# WR_Cute_Carrier_TOP.net
KiCad netlist of a schematic drawn in Altium Designer
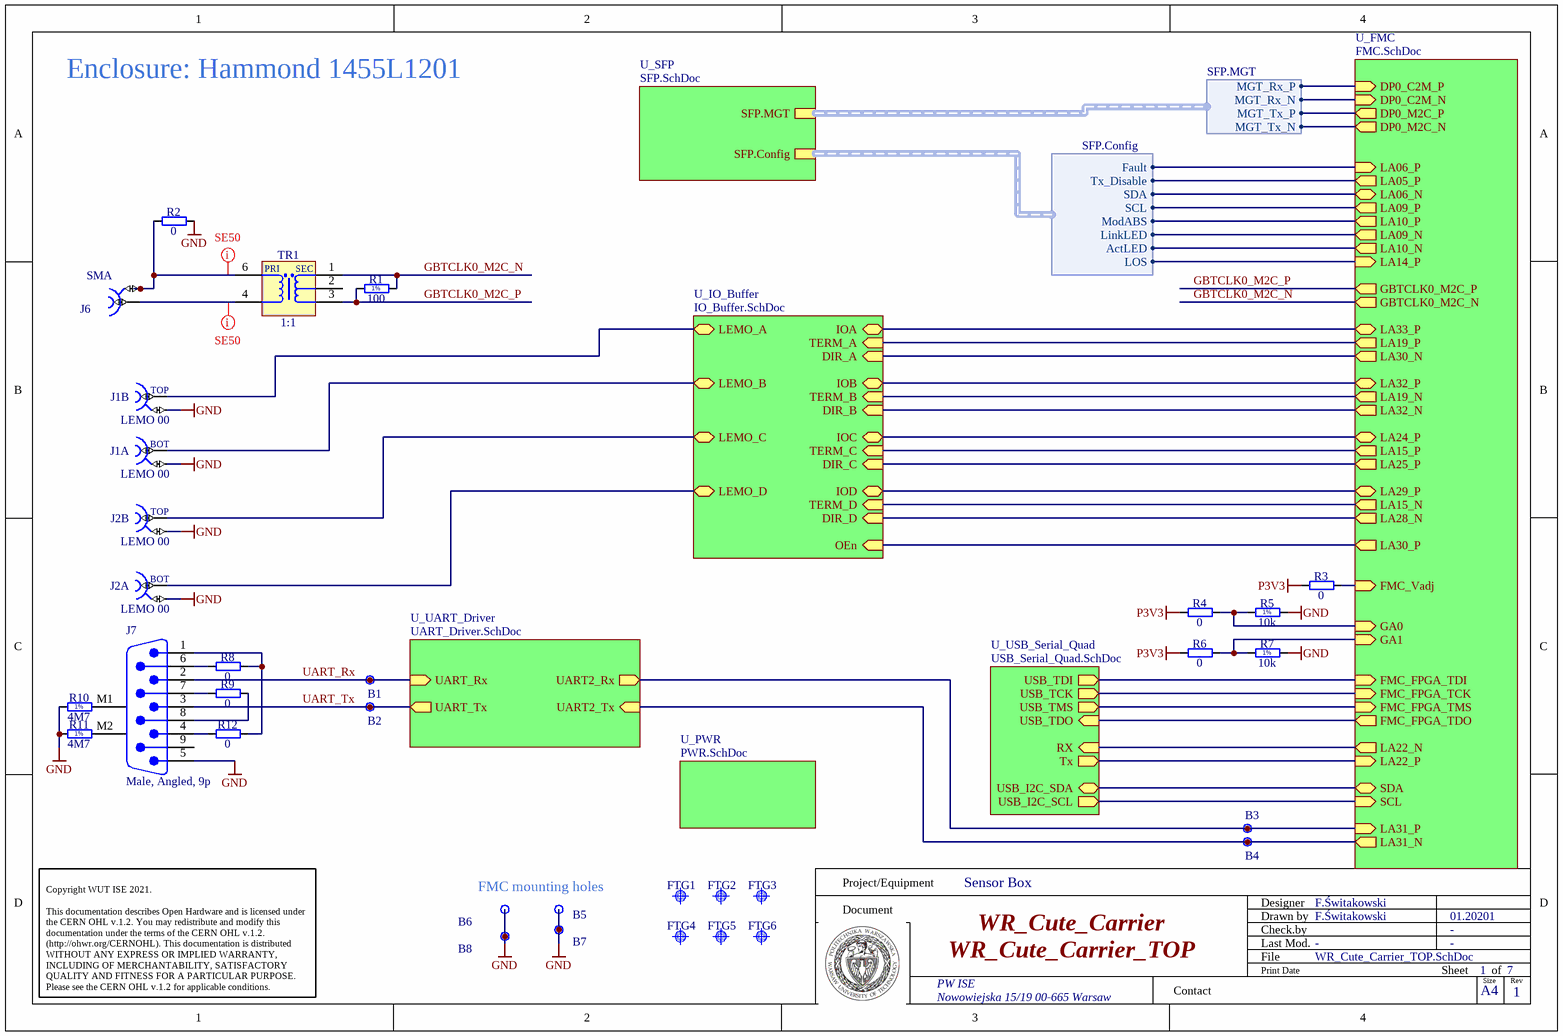
[diagram p0: WR_Cute_Carrier_TOP.SchDoc]

(export (version "E")
  (design (tool "Eeschema 10.0.6"))
  (components
    (comp (ref "B1")
      (value "Plated Hole")
      (footprint "c130h60")
      (description "Single Terminal Socket")
      (fields (field (name "PART NUMBER") "PLATED_HOLE0.6_PAD1.3") (field (name "AUTHOR") "CERN DEM MR"))
      (libsource (lib "Eletro-mechanical") (part "Single Terminal Socket"))
    )
    (comp (ref "B2")
      (value "Plated Hole")
      (footprint "c130h60")
      (description "Single Terminal Socket")
      (fields (field (name "PART NUMBER") "PLATED_HOLE0.6_PAD1.3") (field (name "AUTHOR") "CERN DEM MR"))
      (libsource (lib "Eletro-mechanical") (part "Single Terminal Socket"))
    )
    (comp (ref "B3")
      (value "Plated Hole")
      (footprint "c130h60")
      (description "Single Terminal Socket")
      (fields (field (name "PART NUMBER") "PLATED_HOLE0.6_PAD1.3") (field (name "AUTHOR") "CERN DEM MR"))
      (libsource (lib "Eletro-mechanical") (part "Single Terminal Socket"))
    )
    (comp (ref "B4")
      (value "Plated Hole")
      (footprint "c130h60")
      (description "Single Terminal Socket")
      (fields (field (name "PART NUMBER") "PLATED_HOLE0.6_PAD1.3") (field (name "AUTHOR") "CERN DEM MR"))
      (libsource (lib "Eletro-mechanical") (part "Single Terminal Socket"))
    )
    (comp (ref "B5")
      (value "Plated Hole")
      (footprint "MTG270_500")
      (description "Single Terminal Socket")
      (fields (field (name "PART NUMBER") "PLATED_HOLE2.7_PAD5.0") (field (name "AUTHOR") "CERN DEM JMW"))
      (libsource (lib "Eletro-mechanical") (part "Single Terminal Socket"))
    )
    (comp (ref "B6")
      (value "Plated Hole")
      (footprint "MTG270_500")
      (description "Single Terminal Socket")
      (fields (field (name "PART NUMBER") "PLATED_HOLE2.7_PAD5.0") (field (name "AUTHOR") "CERN DEM JMW"))
      (libsource (lib "Eletro-mechanical") (part "Single Terminal Socket"))
    )
    (comp (ref "B7")
      (value "Plated Hole")
      (footprint "MTG270_500")
      (description "Single Terminal Socket")
      (fields (field (name "PART NUMBER") "PLATED_HOLE2.7_PAD5.0") (field (name "AUTHOR") "CERN DEM JMW"))
      (libsource (lib "Eletro-mechanical") (part "Single Terminal Socket"))
    )
    (comp (ref "B8")
      (value "Plated Hole")
      (footprint "MTG270_500")
      (description "Single Terminal Socket")
      (fields (field (name "PART NUMBER") "PLATED_HOLE2.7_PAD5.0") (field (name "AUTHOR") "CERN DEM JMW"))
      (libsource (lib "Eletro-mechanical") (part "Single Terminal Socket"))
    )
    (comp (ref "FTG1")
      (value "Use only in PCB")
      (footprint "FIDUCIAL_TOP_S100-200")
      (description "Fiducial Target")
      (fields (field (name "PART NUMBER") "FIDUCIAL_TARGET_S100-200") (field (name "AUTHOR") "CERN DEM JLC"))
      (libsource (lib "Eletro-mechanical") (part "Fiducial Target"))
    )
    (comp (ref "FTG2")
      (value "Use only in PCB")
      (footprint "FIDUCIAL_TOP_S100-200")
      (description "Fiducial Target")
      (fields (field (name "PART NUMBER") "FIDUCIAL_TARGET_S100-200") (field (name "AUTHOR") "CERN DEM JLC"))
      (libsource (lib "Eletro-mechanical") (part "Fiducial Target"))
    )
    (comp (ref "FTG3")
      (value "Use only in PCB")
      (footprint "FIDUCIAL_TOP_S100-200")
      (description "Fiducial Target")
      (fields (field (name "PART NUMBER") "FIDUCIAL_TARGET_S100-200") (field (name "AUTHOR") "CERN DEM JLC"))
      (libsource (lib "Eletro-mechanical") (part "Fiducial Target"))
    )
    (comp (ref "FTG4")
      (value "Use only in PCB")
      (footprint "FIDUCIAL_TOP_S100-200")
      (description "Fiducial Target")
      (fields (field (name "PART NUMBER") "FIDUCIAL_TARGET_S100-200") (field (name "AUTHOR") "CERN DEM JLC"))
      (libsource (lib "Eletro-mechanical") (part "Fiducial Target"))
    )
    (comp (ref "FTG5")
      (value "Use only in PCB")
      (footprint "FIDUCIAL_TOP_S100-200")
      (description "Fiducial Target")
      (fields (field (name "PART NUMBER") "FIDUCIAL_TARGET_S100-200") (field (name "AUTHOR") "CERN DEM JLC"))
      (libsource (lib "Eletro-mechanical") (part "Fiducial Target"))
    )
    (comp (ref "FTG6")
      (value "Use only in PCB")
      (footprint "FIDUCIAL_TOP_S100-200")
      (description "Fiducial Target")
      (fields (field (name "PART NUMBER") "FIDUCIAL_TARGET_S100-200") (field (name "AUTHOR") "CERN DEM JLC"))
      (libsource (lib "Eletro-mechanical") (part "Fiducial Target"))
    )
    (comp (ref "J1")
      (value "LEMO 00")
      (footprint "LEMO_EPY.00.250.NTN")
      (description "Dual Female Coax 1-2 Common Shield 3")
      (fields
        (field (name "PART NUMBER") "LEMO_EPY.00.250.NTN")
        (field (name "MANUFACTURER") "LEMO")
        (field (name "AUTHOR") "CERN DEM JMW")
      )
      (libsource (lib "Connectors") (part "LEMO_EPY.00.250.NTN"))
    )
    (comp (ref "J2")
      (value "LEMO 00")
      (footprint "LEMO_EPY.00.250.NTN")
      (description "Dual Female Coax 1-2 Common Shield 3")
      (fields
        (field (name "PART NUMBER") "LEMO_EPY.00.250.NTN")
        (field (name "MANUFACTURER") "LEMO")
        (field (name "AUTHOR") "CERN DEM JMW")
      )
      (libsource (lib "Connectors") (part "LEMO_EPY.00.250.NTN"))
    )
    (comp (ref "J6")
      (value "SMA")
      (footprint "AMPHENOL_132203")
      (fields
        (field (name "PART NUMBER") "AMPHENOL_132203")
        (field (name "MANUFACTURER") "AMPHENOL")
        (field (name "MANUFACTURER PART NUMBER") "132203")
        (field (name "AUTHOR") "CERN DEM MR")
      )
      (libsource (lib "Connectors") (part "Coax_1Female_1Shield"))
    )
    (comp (ref "J7")
      (value "Male, Angled, 9p")
      (footprint "210112013")
      (description "WE-D-SUB Filter Connector, THT, Angled, Male, 9p")
      (fields
        (field (name "MANUFACTURER PART NUMBER") "210112013")
        (field (name "MANUFACTURER") "Wurth Elektronik")
      )
      (libsource (lib "Altium_WE-D-SUB (rev20a)") (part "210112013"))
    )
    (comp (ref "R1")
      (value "100")
      (footprint "RESC2012X60N")
      (description "Resistor - 1%")
      (fields
        (field (name "PART NUMBER") "R0805_100R_1%_0.125W_100PPM")
        (field (name "POWER") "0.125W")
        (field (name "AUTHOR") "CERN DEM JLC")
      )
      (libsource (lib "Resistors") (part "Resistor - 1%"))
    )
    (comp (ref "R2")
      (value "0")
      (footprint "RESC1608X55N")
      (description "Resistor")
      (fields
        (field (name "PART NUMBER") "R0603_0R_JUMPER")
        (field (name "MANUFACTURER") "GENERIC")
        (field (name "AUTHOR") "CERN DEM JLC")
      )
      (libsource (lib "Resistors") (part "Resistor"))
    )
    (comp (ref "R3")
      (value "0")
      (footprint "RESC1608X55N")
      (description "Resistor")
      (fields
        (field (name "PART NUMBER") "R0603_0R_JUMPER")
        (field (name "MANUFACTURER") "GENERIC")
        (field (name "AUTHOR") "CERN DEM JLC")
      )
      (libsource (lib "Resistors") (part "Resistor"))
    )
    (comp (ref "R4")
      (value "0")
      (footprint "RESC1608X55N")
      (description "Resistor")
      (fields
        (field (name "PART NUMBER") "R0603_0R_JUMPER")
        (field (name "MANUFACTURER") "GENERIC")
        (field (name "AUTHOR") "CERN DEM JLC")
      )
      (libsource (lib "Resistors") (part "Resistor"))
    )
    (comp (ref "R5")
      (value "10k")
      (footprint "RESC1608X55N")
      (description "Resistor - 1%")
      (fields
        (field (name "PART NUMBER") "R0603_10K_1%_0.1W_100PPM")
        (field (name "POWER") "0.1W")
        (field (name "AUTHOR") "CERN DEM JLC")
      )
      (libsource (lib "Resistors") (part "Resistor - 1%"))
    )
    (comp (ref "R6")
      (value "0")
      (footprint "RESC1608X55N")
      (description "Resistor")
      (fields
        (field (name "PART NUMBER") "R0603_0R_JUMPER")
        (field (name "MANUFACTURER") "GENERIC")
        (field (name "AUTHOR") "CERN DEM JLC")
      )
      (libsource (lib "Resistors") (part "Resistor"))
    )
    (comp (ref "R7")
      (value "10k")
      (footprint "RESC1608X55N")
      (description "Resistor - 1%")
      (fields
        (field (name "PART NUMBER") "R0603_10K_1%_0.1W_100PPM")
        (field (name "POWER") "0.1W")
        (field (name "AUTHOR") "CERN DEM JLC")
      )
      (libsource (lib "Resistors") (part "Resistor - 1%"))
    )
    (comp (ref "R8")
      (value "0")
      (footprint "RESC1608X55N")
      (description "Resistor")
      (fields
        (field (name "PART NUMBER") "R0603_0R_JUMPER")
        (field (name "MANUFACTURER") "GENERIC")
        (field (name "AUTHOR") "CERN DEM JLC")
      )
      (libsource (lib "Resistors") (part "Resistor"))
    )
    (comp (ref "R9")
      (value "0")
      (footprint "RESC1608X55N")
      (description "Resistor")
      (fields
        (field (name "PART NUMBER") "R0603_0R_JUMPER")
        (field (name "MANUFACTURER") "GENERIC")
        (field (name "AUTHOR") "CERN DEM JLC")
      )
      (libsource (lib "Resistors") (part "Resistor"))
    )
    (comp (ref "R10")
      (value "4M7")
      (footprint "RESC2113X55N")
      (description "Resistor - 1%")
      (fields
        (field (name "PART NUMBER") "R0805_4M7_1%_0.125W_100PPM_VISHAY_CRCW e3")
        (field (name "POWER") "0.125W")
        (field (name "AUTHOR") "CERN DEM BR")
      )
      (libsource (lib "Resistors") (part "Resistor - 1%"))
    )
    (comp (ref "R11")
      (value "4M7")
      (footprint "RESC2113X55N")
      (description "Resistor - 1%")
      (fields
        (field (name "PART NUMBER") "R0805_4M7_1%_0.125W_100PPM_VISHAY_CRCW e3")
        (field (name "POWER") "0.125W")
        (field (name "AUTHOR") "CERN DEM BR")
      )
      (libsource (lib "Resistors") (part "Resistor - 1%"))
    )
    (comp (ref "R12")
      (value "0")
      (footprint "RESC1608X55N")
      (description "Resistor")
      (fields
        (field (name "PART NUMBER") "R0603_0R_JUMPER")
        (field (name "MANUFACTURER") "GENERIC")
        (field (name "AUTHOR") "CERN DEM JLC")
      )
      (libsource (lib "Resistors") (part "Resistor"))
    )
    (comp (ref "TR1")
      (value "1:1")
      (footprint "XFMR_MINI-CIRCUITS_AT1521")
      (description "50 Ohms 3 to 300MHz RF Transformer")
      (fields
        (field (name "PART NUMBER") "XFMR_MINI-CIRCUITS_TC2-1TX+")
        (field (name "MANUFACTURER") "MINI-CIRCUITS")
        (field (name "AUTHOR") "CERN DEM MR")
      )
      (libsource (lib "Inductors & Transformers") (part "XFMR_MINI-CIRCUITS_TC2-1TX+"))
    )
  )
  (nets
    (net (code "8") (name "/FMC_Vadj") (class "Default")
      (node (ref "R3") (pin "2") (pinfunction "2_2") (pintype "passive"))
    )
    (net (code "9") (name "/GA0") (class "Default")
      (node (ref "R4") (pin "2") (pinfunction "2_2") (pintype "passive"))
      (node (ref "R5") (pin "1") (pinfunction "1_1") (pintype "passive"))
    )
    (net (code "10") (name "/GA1") (class "Default")
      (node (ref "R6") (pin "2") (pinfunction "2_2") (pintype "passive"))
      (node (ref "R7") (pin "1") (pinfunction "1_1") (pintype "passive"))
    )
    (net (code "11") (name "/GBTCLK0_M2C_N") (class "Default")
      (node (ref "R1") (pin "2") (pinfunction "2_2") (pintype "passive"))
      (node (ref "TR1") (pin "1") (pinfunction "SDOT_1") (pintype "passive"))
    )
    (net (code "12") (name "/GBTCLK0_M2C_P") (class "Default")
      (node (ref "R1") (pin "1") (pinfunction "1_1") (pintype "passive"))
      (node (ref "TR1") (pin "3") (pinfunction "S_3") (pintype "passive"))
    )
    (net (code "34") (name "/LA31_N") (class "Default")
      (node (ref "B4") (pin "1") (pinfunction "1_1") (pintype "bidirectional"))
    )
    (net (code "36") (name "/LEMO_A") (class "Default")
      (node (ref "J1") (pin "2") (pinfunction "2_2") (pintype "bidirectional"))
    )
    (net (code "37") (name "/LEMO_B") (class "Default")
      (node (ref "J1") (pin "1") (pinfunction "1_1") (pintype "bidirectional"))
    )
    (net (code "38") (name "/LEMO_C") (class "Default")
      (node (ref "J2") (pin "2") (pinfunction "2_2") (pintype "bidirectional"))
    )
    (net (code "39") (name "/LEMO_D") (class "Default")
      (node (ref "J2") (pin "1") (pinfunction "1_1") (pintype "bidirectional"))
    )
    (net (code "42") (name "/UART2_Rx") (class "Default")
      (node (ref "B3") (pin "1") (pinfunction "1_1") (pintype "bidirectional"))
    )
    (net (code "43") (name "/UART_Rx") (class "Default")
      (node (ref "B1") (pin "1") (pinfunction "1_1") (pintype "bidirectional"))
      (node (ref "J7") (pin "2") (pinfunction "2_2") (pintype "passive"))
    )
    (net (code "44") (name "/UART_Tx") (class "Default")
      (node (ref "B2") (pin "1") (pinfunction "1_1") (pintype "bidirectional"))
      (node (ref "J7") (pin "3") (pinfunction "3_3") (pintype "passive"))
    )
    (net (code "51") (name "GND") (class "Default")
      (node (ref "B5") (pin "1") (pinfunction "1_1") (pintype "bidirectional"))
      (node (ref "B6") (pin "1") (pinfunction "1_1") (pintype "bidirectional"))
      (node (ref "B7") (pin "1") (pinfunction "1_1") (pintype "bidirectional"))
      (node (ref "B8") (pin "1") (pinfunction "1_1") (pintype "bidirectional"))
      (node (ref "J1") (pin "3") (pinfunction "3_3") (pintype "bidirectional"))
      (node (ref "J2") (pin "3") (pinfunction "3_3") (pintype "bidirectional"))
      (node (ref "J7") (pin "5") (pinfunction "5_5") (pintype "passive"))
      (node (ref "R10") (pin "1") (pinfunction "1_1") (pintype "passive"))
      (node (ref "R11") (pin "1") (pinfunction "1_1") (pintype "passive"))
      (node (ref "R2") (pin "2") (pinfunction "2_2") (pintype "passive"))
      (node (ref "R5") (pin "2") (pinfunction "2_2") (pintype "passive"))
      (node (ref "R7") (pin "2") (pinfunction "2_2") (pintype "passive"))
    )
    (net (code "52") (name "Net-(J7-Pad1)") (class "Default")
      (node (ref "J7") (pin "1") (pinfunction "1_1") (pintype "passive"))
      (node (ref "R12") (pin "2") (pinfunction "2_2") (pintype "passive"))
      (node (ref "R8") (pin "2") (pinfunction "2_2") (pintype "passive"))
    )
    (net (code "53") (name "Net-(J7-Pad4)") (class "Default")
      (node (ref "J7") (pin "4") (pinfunction "4_4") (pintype "passive"))
      (node (ref "R12") (pin "1") (pinfunction "1_1") (pintype "passive"))
    )
    (net (code "54") (name "Net-(J7-Pad6)") (class "Default")
      (node (ref "J7") (pin "6") (pinfunction "6_6") (pintype "passive"))
      (node (ref "R8") (pin "1") (pinfunction "1_1") (pintype "passive"))
    )
    (net (code "55") (name "Net-(J7-Pad7)") (class "Default")
      (node (ref "J7") (pin "7") (pinfunction "7_7") (pintype "passive"))
      (node (ref "R9") (pin "1") (pinfunction "1_1") (pintype "passive"))
    )
    (net (code "56") (name "Net-(J7-Pad8)") (class "Default")
      (node (ref "J7") (pin "8") (pinfunction "8_8") (pintype "passive"))
      (node (ref "R9") (pin "2") (pinfunction "2_2") (pintype "passive"))
    )
    (net (code "57") (name "Net-(J7-PadM1)") (class "Default")
      (node (ref "J7") (pin "M1") (pinfunction "M1_M1") (pintype "passive"))
      (node (ref "R10") (pin "2") (pinfunction "2_2") (pintype "passive"))
    )
    (net (code "58") (name "Net-(J7-PadM2)") (class "Default")
      (node (ref "J7") (pin "M2") (pinfunction "M2_M2") (pintype "passive"))
      (node (ref "R11") (pin "2") (pinfunction "2_2") (pintype "passive"))
    )
    (net (code "59") (name "Net-(TR1-P)") (class "Default")
      (node (ref "J6") (pin "1") (pinfunction "1_1") (pintype "bidirectional"))
      (node (ref "TR1") (pin "4") (pinfunction "P_4") (pintype "passive"))
    )
    (net (code "60") (name "Net-(TR1-PDOT)") (class "Default")
      (node (ref "J6") (pin "2") (pinfunction "2_2") (pintype "bidirectional"))
      (node (ref "R2") (pin "1") (pinfunction "1_1") (pintype "passive"))
      (node (ref "TR1") (pin "6") (pinfunction "PDOT_6") (pintype "passive"))
    )
    (net (code "61") (name "P3V3") (class "Default")
      (node (ref "R3") (pin "1") (pinfunction "1_1") (pintype "passive"))
      (node (ref "R4") (pin "1") (pinfunction "1_1") (pintype "passive"))
      (node (ref "R6") (pin "1") (pinfunction "1_1") (pintype "passive"))
    )
    (net (code "62") (name "unconnected-(J7-Pad9)") (class "Default")
      (node (ref "J7") (pin "9") (pinfunction "9_9") (pintype "passive"))
    )
    (net (code "63") (name "unconnected-(TR1-NC-Pad2)") (class "Default")
      (node (ref "TR1") (pin "2") (pinfunction "NC_2") (pintype "passive"))
    )
  )
)
